# Sensor_MT9P.net
KiCad netlist of a schematic drawn in EAGLE
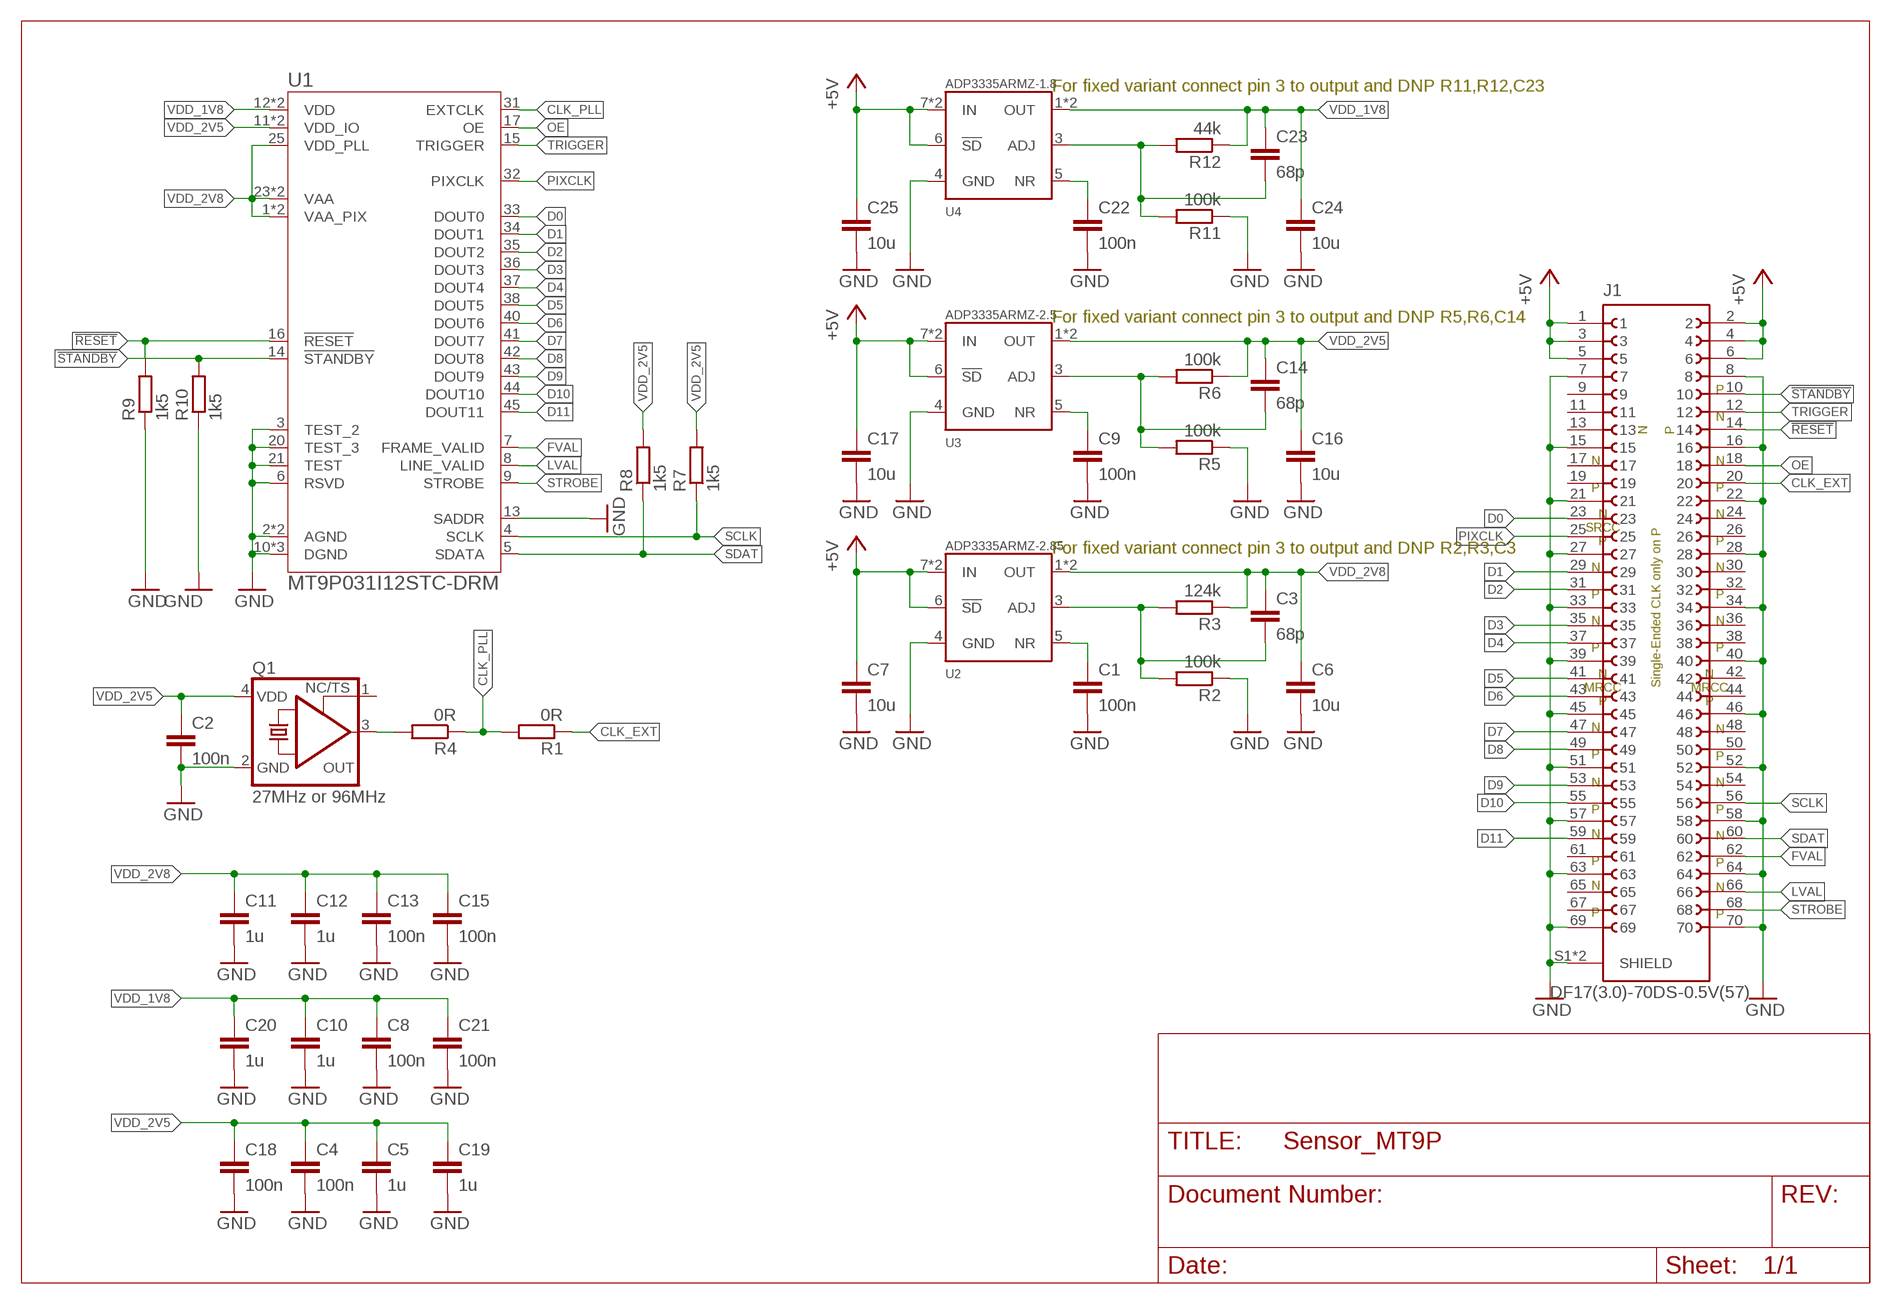
[diagram p0: schematic, sheet 1]

(export (version "E")
  (design (tool "Eeschema 10.0.6"))
  (components
    (comp (ref "C1")
      (value "100n")
      (footprint "eagle-import:C0402")
      (libsource (lib "eagle-import") (part "rcl_334_C-EUC0402"))
    )
    (comp (ref "C2")
      (value "100n")
      (footprint "eagle-import:C0402")
      (libsource (lib "eagle-import") (part "C-EUC0402"))
    )
    (comp (ref "C3")
      (value "68p")
      (footprint "eagle-import:C0402")
      (libsource (lib "eagle-import") (part "rcl_334_C-EUC0402"))
    )
    (comp (ref "C4")
      (value "100n")
      (footprint "eagle-import:C0402")
      (libsource (lib "eagle-import") (part "rcl_334_C-EUC0402"))
    )
    (comp (ref "C5")
      (value "1u")
      (footprint "eagle-import:C0402")
      (libsource (lib "eagle-import") (part "rcl_334_C-EUC0402"))
    )
    (comp (ref "C6")
      (value "10u")
      (footprint "eagle-import:C0603")
      (libsource (lib "eagle-import") (part "rcl_334_C-EUC0603"))
    )
    (comp (ref "C7")
      (value "10u")
      (footprint "eagle-import:C0603")
      (libsource (lib "eagle-import") (part "rcl_334_C-EUC0603"))
    )
    (comp (ref "C8")
      (value "100n")
      (footprint "eagle-import:C0402")
      (libsource (lib "eagle-import") (part "rcl_334_C-EUC0402"))
    )
    (comp (ref "C9")
      (value "100n")
      (footprint "eagle-import:C0402")
      (libsource (lib "eagle-import") (part "rcl_334_C-EUC0402"))
    )
    (comp (ref "C10")
      (value "1u")
      (footprint "eagle-import:C0402")
      (libsource (lib "eagle-import") (part "rcl_334_C-EUC0402"))
    )
    (comp (ref "C11")
      (value "1u")
      (footprint "eagle-import:C0402")
      (libsource (lib "eagle-import") (part "rcl_334_C-EUC0402"))
    )
    (comp (ref "C12")
      (value "1u")
      (footprint "eagle-import:C0402")
      (libsource (lib "eagle-import") (part "rcl_334_C-EUC0402"))
    )
    (comp (ref "C13")
      (value "100n")
      (footprint "eagle-import:C0402")
      (libsource (lib "eagle-import") (part "rcl_334_C-EUC0402"))
    )
    (comp (ref "C14")
      (value "68p")
      (footprint "eagle-import:C0402")
      (libsource (lib "eagle-import") (part "rcl_334_C-EUC0402"))
    )
    (comp (ref "C15")
      (value "100n")
      (footprint "eagle-import:C0402")
      (libsource (lib "eagle-import") (part "rcl_334_C-EUC0402"))
    )
    (comp (ref "C16")
      (value "10u")
      (footprint "eagle-import:C0603")
      (libsource (lib "eagle-import") (part "rcl_334_C-EUC0603"))
    )
    (comp (ref "C17")
      (value "10u")
      (footprint "eagle-import:C0603")
      (libsource (lib "eagle-import") (part "rcl_334_C-EUC0603"))
    )
    (comp (ref "C18")
      (value "100n")
      (footprint "eagle-import:C0402")
      (libsource (lib "eagle-import") (part "rcl_334_C-EUC0402"))
    )
    (comp (ref "C19")
      (value "1u")
      (footprint "eagle-import:C0402")
      (libsource (lib "eagle-import") (part "rcl_334_C-EUC0402"))
    )
    (comp (ref "C20")
      (value "1u")
      (footprint "eagle-import:C0402")
      (libsource (lib "eagle-import") (part "rcl_334_C-EUC0402"))
    )
    (comp (ref "C21")
      (value "100n")
      (footprint "eagle-import:C0402")
      (libsource (lib "eagle-import") (part "rcl_334_C-EUC0402"))
    )
    (comp (ref "C22")
      (value "100n")
      (footprint "eagle-import:C0402")
      (libsource (lib "eagle-import") (part "rcl_334_C-EUC0402"))
    )
    (comp (ref "C23")
      (value "68p")
      (footprint "eagle-import:C0402")
      (libsource (lib "eagle-import") (part "rcl_334_C-EUC0402"))
    )
    (comp (ref "C24")
      (value "10u")
      (footprint "eagle-import:C0603")
      (libsource (lib "eagle-import") (part "rcl_334_C-EUC0603"))
    )
    (comp (ref "C25")
      (value "10u")
      (footprint "eagle-import:C0603")
      (libsource (lib "eagle-import") (part "rcl_334_C-EUC0603"))
    )
    (comp (ref "J1")
      (value "DF17(3.0)-70DS-0.5V(57)")
      (footprint "eagle-import:DF17(3.0)-70DS-0.5V(57)")
      (libsource (lib "eagle-import") (part "DF17(3.0)-70DS-0.5V(57)"))
    )
    (comp (ref "Q1")
      (value "27MHz or 96MHz")
      (footprint "eagle-import:3.2X2.5_KXO-V96")
      (libsource (lib "eagle-import") (part "KXO-PXO/XO-V96"))
    )
    (comp (ref "R1")
      (value "0R")
      (footprint "eagle-import:R0402")
      (libsource (lib "eagle-import") (part "R-EU_R0402"))
    )
    (comp (ref "R2")
      (value "100k")
      (footprint "eagle-import:R0402")
      (libsource (lib "eagle-import") (part "R-EU_R0402"))
    )
    (comp (ref "R3")
      (value "124k")
      (footprint "eagle-import:R0402")
      (libsource (lib "eagle-import") (part "R-EU_R0402"))
    )
    (comp (ref "R4")
      (value "0R")
      (footprint "eagle-import:R0402")
      (libsource (lib "eagle-import") (part "R-EU_R0402"))
    )
    (comp (ref "R5")
      (value "100k")
      (footprint "eagle-import:R0402")
      (libsource (lib "eagle-import") (part "R-EU_R0402"))
    )
    (comp (ref "R6")
      (value "100k")
      (footprint "eagle-import:R0402")
      (libsource (lib "eagle-import") (part "R-EU_R0402"))
    )
    (comp (ref "R7")
      (value "1k5")
      (footprint "eagle-import:R0402")
      (libsource (lib "eagle-import") (part "R-EU_R0402"))
    )
    (comp (ref "R8")
      (value "1k5")
      (footprint "eagle-import:R0402")
      (libsource (lib "eagle-import") (part "R-EU_R0402"))
    )
    (comp (ref "R9")
      (value "1k5")
      (footprint "eagle-import:R0402")
      (libsource (lib "eagle-import") (part "R-EU_R0402"))
    )
    (comp (ref "R10")
      (value "1k5")
      (footprint "eagle-import:R0402")
      (libsource (lib "eagle-import") (part "R-EU_R0402"))
    )
    (comp (ref "R11")
      (value "100k")
      (footprint "eagle-import:R0402")
      (libsource (lib "eagle-import") (part "R-EU_R0402"))
    )
    (comp (ref "R12")
      (value "44k")
      (footprint "eagle-import:R0402")
      (libsource (lib "eagle-import") (part "R-EU_R0402"))
    )
    (comp (ref "U1")
      (value "MT9P031I12STC-DRM")
      (footprint "eagle-import:ILCC48_10X10_847AA-O_OSI-M")
      (fields (field (name "MPN") "MT9P031I12STC-DR"))
      (libsource (lib "eagle-import") (part "MT9P031I12STC-DRM"))
    )
    (comp (ref "U2")
      (value "ADP3335ARMZ-2.85")
      (footprint "eagle-import:MSOP08")
      (libsource (lib "eagle-import") (part "NCP3335"))
    )
    (comp (ref "U3")
      (value "ADP3335ARMZ-2.5")
      (footprint "eagle-import:MSOP08")
      (libsource (lib "eagle-import") (part "NCP3335"))
    )
    (comp (ref "U4")
      (value "ADP3335ARMZ-1.8")
      (footprint "eagle-import:MSOP08")
      (libsource (lib "eagle-import") (part "NCP3335"))
    )
  )
  (nets
    (net (code "1") (name "+5V") (class "Default")
      (node (ref "C17") (pin "1") (pinfunction "1_1") (pintype "passive"))
      (node (ref "C25") (pin "1") (pinfunction "1_1") (pintype "passive"))
      (node (ref "C7") (pin "1") (pinfunction "1_1") (pintype "passive"))
      (node (ref "J1") (pin "1") (pinfunction "1_1") (pintype "passive"))
      (node (ref "J1") (pin "2") (pinfunction "2_2") (pintype "passive"))
      (node (ref "J1") (pin "3") (pinfunction "3_3") (pintype "passive"))
      (node (ref "J1") (pin "4") (pinfunction "4_4") (pintype "passive"))
      (node (ref "J1") (pin "5") (pinfunction "5_5") (pintype "passive"))
      (node (ref "J1") (pin "6") (pinfunction "6_6") (pintype "passive"))
      (node (ref "U2") (pin "6") (pinfunction "~{SD}_6") (pintype "input"))
      (node (ref "U2") (pin "7") (pinfunction "IN_7") (pintype "power_in"))
      (node (ref "U2") (pin "8") (pinfunction "IN_8") (pintype "power_in"))
      (node (ref "U3") (pin "6") (pinfunction "~{SD}_6") (pintype "input"))
      (node (ref "U3") (pin "7") (pinfunction "IN_7") (pintype "power_in"))
      (node (ref "U3") (pin "8") (pinfunction "IN_8") (pintype "power_in"))
      (node (ref "U4") (pin "6") (pinfunction "~{SD}_6") (pintype "input"))
      (node (ref "U4") (pin "7") (pinfunction "IN_7") (pintype "power_in"))
      (node (ref "U4") (pin "8") (pinfunction "IN_8") (pintype "power_in"))
    )
    (net (code "2") (name "/~{RESET}") (class "Default")
      (node (ref "J1") (pin "14") (pinfunction "14_14") (pintype "passive"))
      (node (ref "R9") (pin "2") (pinfunction "2_2") (pintype "passive"))
      (node (ref "U1") (pin "16") (pinfunction "~{RESET}_16") (pintype "passive"))
    )
    (net (code "3") (name "/~{STANDBY}") (class "Default")
      (node (ref "J1") (pin "10") (pinfunction "10_10") (pintype "passive"))
      (node (ref "R10") (pin "2") (pinfunction "2_2") (pintype "passive"))
      (node (ref "U1") (pin "14") (pinfunction "~{STANDBY}_14") (pintype "passive"))
    )
    (net (code "4") (name "CLK_EXT") (class "Default")
      (node (ref "J1") (pin "20") (pinfunction "20_20") (pintype "passive"))
      (node (ref "R1") (pin "1") (pinfunction "1_1") (pintype "passive"))
    )
    (net (code "5") (name "CLK_PLL") (class "Default")
      (node (ref "R1") (pin "2") (pinfunction "2_2") (pintype "passive"))
      (node (ref "R4") (pin "1") (pinfunction "1_1") (pintype "passive"))
      (node (ref "U1") (pin "31") (pinfunction "EXTCLK_31") (pintype "passive"))
    )
    (net (code "6") (name "D0") (class "Default")
      (node (ref "J1") (pin "23") (pinfunction "23_23") (pintype "passive"))
      (node (ref "U1") (pin "33") (pinfunction "DOUT0_33") (pintype "output"))
    )
    (net (code "7") (name "D1") (class "Default")
      (node (ref "J1") (pin "29") (pinfunction "29_29") (pintype "passive"))
      (node (ref "U1") (pin "34") (pinfunction "DOUT1_34") (pintype "output"))
    )
    (net (code "8") (name "D2") (class "Default")
      (node (ref "J1") (pin "31") (pinfunction "31_31") (pintype "passive"))
      (node (ref "U1") (pin "35") (pinfunction "DOUT2_35") (pintype "output"))
    )
    (net (code "9") (name "D3") (class "Default")
      (node (ref "J1") (pin "35") (pinfunction "35_35") (pintype "passive"))
      (node (ref "U1") (pin "36") (pinfunction "DOUT3_36") (pintype "output"))
    )
    (net (code "10") (name "D4") (class "Default")
      (node (ref "J1") (pin "37") (pinfunction "37_37") (pintype "passive"))
      (node (ref "U1") (pin "37") (pinfunction "DOUT4_37") (pintype "output"))
    )
    (net (code "11") (name "D5") (class "Default")
      (node (ref "J1") (pin "41") (pinfunction "41_41") (pintype "passive"))
      (node (ref "U1") (pin "38") (pinfunction "DOUT5_38") (pintype "output"))
    )
    (net (code "12") (name "D6") (class "Default")
      (node (ref "J1") (pin "43") (pinfunction "43_43") (pintype "passive"))
      (node (ref "U1") (pin "40") (pinfunction "DOUT6_40") (pintype "output"))
    )
    (net (code "13") (name "D7") (class "Default")
      (node (ref "J1") (pin "47") (pinfunction "47_47") (pintype "passive"))
      (node (ref "U1") (pin "41") (pinfunction "DOUT7_41") (pintype "output"))
    )
    (net (code "14") (name "D8") (class "Default")
      (node (ref "J1") (pin "49") (pinfunction "49_49") (pintype "passive"))
      (node (ref "U1") (pin "42") (pinfunction "DOUT8_42") (pintype "output"))
    )
    (net (code "15") (name "D9") (class "Default")
      (node (ref "J1") (pin "53") (pinfunction "53_53") (pintype "passive"))
      (node (ref "U1") (pin "43") (pinfunction "DOUT9_43") (pintype "output"))
    )
    (net (code "16") (name "D10") (class "Default")
      (node (ref "J1") (pin "55") (pinfunction "55_55") (pintype "passive"))
      (node (ref "U1") (pin "44") (pinfunction "DOUT10_44") (pintype "output"))
    )
    (net (code "17") (name "D11") (class "Default")
      (node (ref "J1") (pin "59") (pinfunction "59_59") (pintype "passive"))
      (node (ref "U1") (pin "45") (pinfunction "DOUT11_45") (pintype "output"))
    )
    (net (code "18") (name "FVAL") (class "Default")
      (node (ref "J1") (pin "62") (pinfunction "62_62") (pintype "passive"))
      (node (ref "U1") (pin "7") (pinfunction "FRAME_VALID_7") (pintype "passive"))
    )
    (net (code "19") (name "GND") (class "Default")
      (node (ref "C1") (pin "2") (pinfunction "2_2") (pintype "passive"))
      (node (ref "C10") (pin "2") (pinfunction "2_2") (pintype "passive"))
      (node (ref "C11") (pin "2") (pinfunction "2_2") (pintype "passive"))
      (node (ref "C12") (pin "2") (pinfunction "2_2") (pintype "passive"))
      (node (ref "C13") (pin "2") (pinfunction "2_2") (pintype "passive"))
      (node (ref "C15") (pin "2") (pinfunction "2_2") (pintype "passive"))
      (node (ref "C16") (pin "2") (pinfunction "2_2") (pintype "passive"))
      (node (ref "C17") (pin "2") (pinfunction "2_2") (pintype "passive"))
      (node (ref "C18") (pin "2") (pinfunction "2_2") (pintype "passive"))
      (node (ref "C19") (pin "2") (pinfunction "2_2") (pintype "passive"))
      (node (ref "C2") (pin "2") (pinfunction "2_2") (pintype "passive"))
      (node (ref "C20") (pin "2") (pinfunction "2_2") (pintype "passive"))
      (node (ref "C21") (pin "2") (pinfunction "2_2") (pintype "passive"))
      (node (ref "C22") (pin "2") (pinfunction "2_2") (pintype "passive"))
      (node (ref "C24") (pin "2") (pinfunction "2_2") (pintype "passive"))
      (node (ref "C25") (pin "2") (pinfunction "2_2") (pintype "passive"))
      (node (ref "C4") (pin "2") (pinfunction "2_2") (pintype "passive"))
      (node (ref "C5") (pin "2") (pinfunction "2_2") (pintype "passive"))
      (node (ref "C6") (pin "2") (pinfunction "2_2") (pintype "passive"))
      (node (ref "C7") (pin "2") (pinfunction "2_2") (pintype "passive"))
      (node (ref "C8") (pin "2") (pinfunction "2_2") (pintype "passive"))
      (node (ref "C9") (pin "2") (pinfunction "2_2") (pintype "passive"))
      (node (ref "J1") (pin "15") (pinfunction "15_15") (pintype "passive"))
      (node (ref "J1") (pin "16") (pinfunction "16_16") (pintype "passive"))
      (node (ref "J1") (pin "21") (pinfunction "21_21") (pintype "passive"))
      (node (ref "J1") (pin "22") (pinfunction "22_22") (pintype "passive"))
      (node (ref "J1") (pin "27") (pinfunction "27_27") (pintype "passive"))
      (node (ref "J1") (pin "28") (pinfunction "28_28") (pintype "passive"))
      (node (ref "J1") (pin "33") (pinfunction "33_33") (pintype "passive"))
      (node (ref "J1") (pin "34") (pinfunction "34_34") (pintype "passive"))
      (node (ref "J1") (pin "39") (pinfunction "39_39") (pintype "passive"))
      (node (ref "J1") (pin "40") (pinfunction "40_40") (pintype "passive"))
      (node (ref "J1") (pin "45") (pinfunction "45_45") (pintype "passive"))
      (node (ref "J1") (pin "46") (pinfunction "46_46") (pintype "passive"))
      (node (ref "J1") (pin "51") (pinfunction "51_51") (pintype "passive"))
      (node (ref "J1") (pin "52") (pinfunction "52_52") (pintype "passive"))
      (node (ref "J1") (pin "57") (pinfunction "57_57") (pintype "passive"))
      (node (ref "J1") (pin "58") (pinfunction "58_58") (pintype "passive"))
      (node (ref "J1") (pin "63") (pinfunction "63_63") (pintype "passive"))
      (node (ref "J1") (pin "64") (pinfunction "64_64") (pintype "passive"))
      (node (ref "J1") (pin "69") (pinfunction "69_69") (pintype "passive"))
      (node (ref "J1") (pin "7") (pinfunction "7_7") (pintype "passive"))
      (node (ref "J1") (pin "70") (pinfunction "70_70") (pintype "passive"))
      (node (ref "J1") (pin "8") (pinfunction "8_8") (pintype "passive"))
      (node (ref "J1") (pin "S1") (pinfunction "SHIELD_S1") (pintype "passive"))
      (node (ref "J1") (pin "S2") (pinfunction "SHIELD_S2") (pintype "passive"))
      (node (ref "Q1") (pin "2") (pinfunction "GND_2") (pintype "power_in"))
      (node (ref "R10") (pin "1") (pinfunction "1_1") (pintype "passive"))
      (node (ref "R11") (pin "1") (pinfunction "1_1") (pintype "passive"))
      (node (ref "R2") (pin "1") (pinfunction "1_1") (pintype "passive"))
      (node (ref "R5") (pin "1") (pinfunction "1_1") (pintype "passive"))
      (node (ref "R9") (pin "1") (pinfunction "1_1") (pintype "passive"))
      (node (ref "U1") (pin "10") (pinfunction "DGND_10") (pintype "passive"))
      (node (ref "U1") (pin "13") (pinfunction "SADDR_13") (pintype "passive"))
      (node (ref "U1") (pin "2") (pinfunction "AGND_2") (pintype "passive"))
      (node (ref "U1") (pin "20") (pinfunction "TEST_3_20") (pintype "passive"))
      (node (ref "U1") (pin "21") (pinfunction "TEST_21") (pintype "passive"))
      (node (ref "U1") (pin "22") (pinfunction "AGND_22") (pintype "passive"))
      (node (ref "U1") (pin "26") (pinfunction "DGND_26") (pintype "passive"))
      (node (ref "U1") (pin "3") (pinfunction "TEST_2_3") (pintype "passive"))
      (node (ref "U1") (pin "46") (pinfunction "DGND_46") (pintype "passive"))
      (node (ref "U1") (pin "6") (pinfunction "RSVD_6") (pintype "passive"))
      (node (ref "U2") (pin "4") (pinfunction "GND_4") (pintype "power_in"))
      (node (ref "U3") (pin "4") (pinfunction "GND_4") (pintype "power_in"))
      (node (ref "U4") (pin "4") (pinfunction "GND_4") (pintype "power_in"))
    )
    (net (code "20") (name "LVAL") (class "Default")
      (node (ref "J1") (pin "66") (pinfunction "66_66") (pintype "passive"))
      (node (ref "U1") (pin "8") (pinfunction "LINE_VALID_8") (pintype "passive"))
    )
    (net (code "21") (name "Net-(Q1-OUT)") (class "Default")
      (node (ref "Q1") (pin "3") (pinfunction "OUT_3") (pintype "output"))
      (node (ref "R4") (pin "2") (pinfunction "2_2") (pintype "passive"))
    )
    (net (code "22") (name "Net-(U2-ADJ)") (class "Default")
      (node (ref "C3") (pin "2") (pinfunction "2_2") (pintype "passive"))
      (node (ref "R2") (pin "2") (pinfunction "2_2") (pintype "passive"))
      (node (ref "R3") (pin "2") (pinfunction "2_2") (pintype "passive"))
      (node (ref "U2") (pin "3") (pinfunction "ADJ_3") (pintype "passive"))
    )
    (net (code "23") (name "Net-(U2-NR)") (class "Default")
      (node (ref "C1") (pin "1") (pinfunction "1_1") (pintype "passive"))
      (node (ref "U2") (pin "5") (pinfunction "NR_5") (pintype "passive"))
    )
    (net (code "24") (name "Net-(U3-ADJ)") (class "Default")
      (node (ref "C14") (pin "2") (pinfunction "2_2") (pintype "passive"))
      (node (ref "R5") (pin "2") (pinfunction "2_2") (pintype "passive"))
      (node (ref "R6") (pin "2") (pinfunction "2_2") (pintype "passive"))
      (node (ref "U3") (pin "3") (pinfunction "ADJ_3") (pintype "passive"))
    )
    (net (code "25") (name "Net-(U3-NR)") (class "Default")
      (node (ref "C9") (pin "1") (pinfunction "1_1") (pintype "passive"))
      (node (ref "U3") (pin "5") (pinfunction "NR_5") (pintype "passive"))
    )
    (net (code "26") (name "Net-(U4-ADJ)") (class "Default")
      (node (ref "C23") (pin "2") (pinfunction "2_2") (pintype "passive"))
      (node (ref "R11") (pin "2") (pinfunction "2_2") (pintype "passive"))
      (node (ref "R12") (pin "2") (pinfunction "2_2") (pintype "passive"))
      (node (ref "U4") (pin "3") (pinfunction "ADJ_3") (pintype "passive"))
    )
    (net (code "27") (name "Net-(U4-NR)") (class "Default")
      (node (ref "C22") (pin "1") (pinfunction "1_1") (pintype "passive"))
      (node (ref "U4") (pin "5") (pinfunction "NR_5") (pintype "passive"))
    )
    (net (code "28") (name "OE") (class "Default")
      (node (ref "J1") (pin "18") (pinfunction "18_18") (pintype "passive"))
      (node (ref "U1") (pin "17") (pinfunction "OE_17") (pintype "passive"))
    )
    (net (code "29") (name "PIXCLK") (class "Default")
      (node (ref "J1") (pin "25") (pinfunction "25_25") (pintype "passive"))
      (node (ref "U1") (pin "32") (pinfunction "PIXCLK_32") (pintype "passive"))
    )
    (net (code "30") (name "SCLK") (class "Default")
      (node (ref "J1") (pin "56") (pinfunction "56_56") (pintype "passive"))
      (node (ref "R7") (pin "1") (pinfunction "1_1") (pintype "passive"))
      (node (ref "U1") (pin "4") (pinfunction "SCLK_4") (pintype "passive"))
    )
    (net (code "31") (name "SDAT") (class "Default")
      (node (ref "J1") (pin "60") (pinfunction "60_60") (pintype "passive"))
      (node (ref "R8") (pin "1") (pinfunction "1_1") (pintype "passive"))
      (node (ref "U1") (pin "5") (pinfunction "SDATA_5") (pintype "passive"))
    )
    (net (code "32") (name "STROBE") (class "Default")
      (node (ref "J1") (pin "68") (pinfunction "68_68") (pintype "passive"))
      (node (ref "U1") (pin "9") (pinfunction "STROBE_9") (pintype "passive"))
    )
    (net (code "33") (name "TRIGGER") (class "Default")
      (node (ref "J1") (pin "12") (pinfunction "12_12") (pintype "passive"))
      (node (ref "U1") (pin "15") (pinfunction "TRIGGER_15") (pintype "passive"))
    )
    (net (code "34") (name "VDD_1V8") (class "Default")
      (node (ref "C10") (pin "1") (pinfunction "1_1") (pintype "passive"))
      (node (ref "C20") (pin "1") (pinfunction "1_1") (pintype "passive"))
      (node (ref "C21") (pin "1") (pinfunction "1_1") (pintype "passive"))
      (node (ref "C23") (pin "1") (pinfunction "1_1") (pintype "passive"))
      (node (ref "C24") (pin "1") (pinfunction "1_1") (pintype "passive"))
      (node (ref "C8") (pin "1") (pinfunction "1_1") (pintype "passive"))
      (node (ref "R12") (pin "1") (pinfunction "1_1") (pintype "passive"))
      (node (ref "U1") (pin "12") (pinfunction "VDD_12") (pintype "power_in"))
      (node (ref "U1") (pin "47") (pinfunction "VDD_47") (pintype "power_in"))
      (node (ref "U4") (pin "1") (pinfunction "OUT_1") (pintype "power_in"))
      (node (ref "U4") (pin "2") (pinfunction "OUT_2") (pintype "power_in"))
    )
    (net (code "35") (name "VDD_2V5") (class "Default")
      (node (ref "C14") (pin "1") (pinfunction "1_1") (pintype "passive"))
      (node (ref "C16") (pin "1") (pinfunction "1_1") (pintype "passive"))
      (node (ref "C18") (pin "1") (pinfunction "1_1") (pintype "passive"))
      (node (ref "C19") (pin "1") (pinfunction "1_1") (pintype "passive"))
      (node (ref "C2") (pin "1") (pinfunction "1_1") (pintype "passive"))
      (node (ref "C4") (pin "1") (pinfunction "1_1") (pintype "passive"))
      (node (ref "C5") (pin "1") (pinfunction "1_1") (pintype "passive"))
      (node (ref "Q1") (pin "4") (pinfunction "VDD_4") (pintype "power_in"))
      (node (ref "R6") (pin "1") (pinfunction "1_1") (pintype "passive"))
      (node (ref "R7") (pin "2") (pinfunction "2_2") (pintype "passive"))
      (node (ref "R8") (pin "2") (pinfunction "2_2") (pintype "passive"))
      (node (ref "U1") (pin "11") (pinfunction "VDD_IO_11") (pintype "power_in"))
      (node (ref "U1") (pin "39") (pinfunction "VDD_IO_39") (pintype "power_in"))
      (node (ref "U3") (pin "1") (pinfunction "OUT_1") (pintype "power_in"))
      (node (ref "U3") (pin "2") (pinfunction "OUT_2") (pintype "power_in"))
    )
    (net (code "36") (name "VDD_2V8") (class "Default")
      (node (ref "C11") (pin "1") (pinfunction "1_1") (pintype "passive"))
      (node (ref "C12") (pin "1") (pinfunction "1_1") (pintype "passive"))
      (node (ref "C13") (pin "1") (pinfunction "1_1") (pintype "passive"))
      (node (ref "C15") (pin "1") (pinfunction "1_1") (pintype "passive"))
      (node (ref "C3") (pin "1") (pinfunction "1_1") (pintype "passive"))
      (node (ref "C6") (pin "1") (pinfunction "1_1") (pintype "passive"))
      (node (ref "R3") (pin "1") (pinfunction "1_1") (pintype "passive"))
      (node (ref "U1") (pin "1") (pinfunction "VAA_PIX_1") (pintype "passive"))
      (node (ref "U1") (pin "23") (pinfunction "VAA_23") (pintype "passive"))
      (node (ref "U1") (pin "24") (pinfunction "VAA_24") (pintype "passive"))
      (node (ref "U1") (pin "25") (pinfunction "VDD_PLL_25") (pintype "power_in"))
      (node (ref "U1") (pin "48") (pinfunction "VAA_PIX_48") (pintype "passive"))
      (node (ref "U2") (pin "1") (pinfunction "OUT_1") (pintype "power_in"))
      (node (ref "U2") (pin "2") (pinfunction "OUT_2") (pintype "power_in"))
    )
    (net (code "37") (name "unconnected-(J1-Pad9)") (class "Default")
      (node (ref "J1") (pin "9") (pinfunction "9_9") (pintype "passive"))
    )
    (net (code "38") (name "unconnected-(J1-Pad11)") (class "Default")
      (node (ref "J1") (pin "11") (pinfunction "11_11") (pintype "passive"))
    )
    (net (code "39") (name "unconnected-(J1-Pad13)") (class "Default")
      (node (ref "J1") (pin "13") (pinfunction "13_13") (pintype "passive"))
    )
    (net (code "40") (name "unconnected-(J1-Pad17)") (class "Default")
      (node (ref "J1") (pin "17") (pinfunction "17_17") (pintype "passive"))
    )
    (net (code "41") (name "unconnected-(J1-Pad19)") (class "Default")
      (node (ref "J1") (pin "19") (pinfunction "19_19") (pintype "passive"))
    )
    (net (code "42") (name "unconnected-(J1-Pad24)") (class "Default")
      (node (ref "J1") (pin "24") (pinfunction "24_24") (pintype "passive"))
    )
    (net (code "43") (name "unconnected-(J1-Pad26)") (class "Default")
      (node (ref "J1") (pin "26") (pinfunction "26_26") (pintype "passive"))
    )
    (net (code "44") (name "unconnected-(J1-Pad30)") (class "Default")
      (node (ref "J1") (pin "30") (pinfunction "30_30") (pintype "passive"))
    )
    (net (code "45") (name "unconnected-(J1-Pad32)") (class "Default")
      (node (ref "J1") (pin "32") (pinfunction "32_32") (pintype "passive"))
    )
    (net (code "46") (name "unconnected-(J1-Pad36)") (class "Default")
      (node (ref "J1") (pin "36") (pinfunction "36_36") (pintype "passive"))
    )
    (net (code "47") (name "unconnected-(J1-Pad38)") (class "Default")
      (node (ref "J1") (pin "38") (pinfunction "38_38") (pintype "passive"))
    )
    (net (code "48") (name "unconnected-(J1-Pad42)") (class "Default")
      (node (ref "J1") (pin "42") (pinfunction "42_42") (pintype "passive"))
    )
    (net (code "49") (name "unconnected-(J1-Pad44)") (class "Default")
      (node (ref "J1") (pin "44") (pinfunction "44_44") (pintype "passive"))
    )
    (net (code "50") (name "unconnected-(J1-Pad48)") (class "Default")
      (node (ref "J1") (pin "48") (pinfunction "48_48") (pintype "passive"))
    )
    (net (code "51") (name "unconnected-(J1-Pad50)") (class "Default")
      (node (ref "J1") (pin "50") (pinfunction "50_50") (pintype "passive"))
    )
    (net (code "52") (name "unconnected-(J1-Pad54)") (class "Default")
      (node (ref "J1") (pin "54") (pinfunction "54_54") (pintype "passive"))
    )
    (net (code "53") (name "unconnected-(J1-Pad61)") (class "Default")
      (node (ref "J1") (pin "61") (pinfunction "61_61") (pintype "passive"))
    )
    (net (code "54") (name "unconnected-(J1-Pad65)") (class "Default")
      (node (ref "J1") (pin "65") (pinfunction "65_65") (pintype "passive"))
    )
    (net (code "55") (name "unconnected-(J1-Pad67)") (class "Default")
      (node (ref "J1") (pin "67") (pinfunction "67_67") (pintype "passive"))
    )
    (net (code "56") (name "unconnected-(Q1-TS-Pad1)") (class "Default")
      (node (ref "Q1") (pin "1") (pinfunction "TS_1") (pintype "passive"))
    )
  )
)
